# IR_detector_pcb.net
KiCad netlist of a schematic drawn in EAGLE
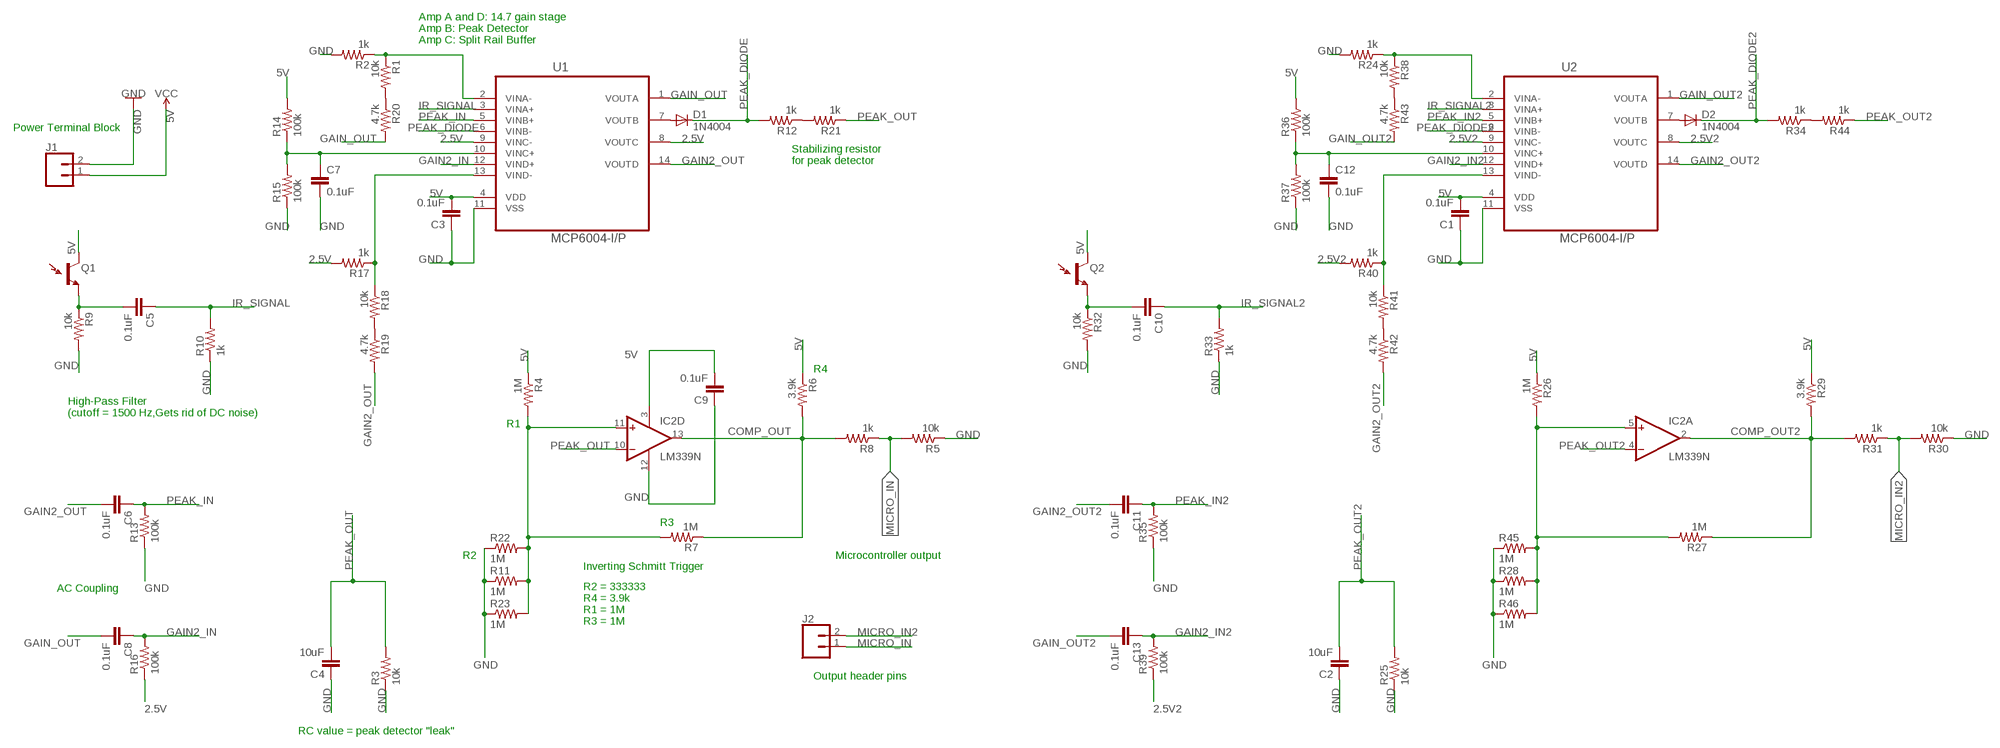
[diagram p0: schematic, sheet 1]

(export (version "E")
  (design (tool "Eeschema 10.0.6"))
  (components
    (comp (ref "C1")
      (value "0.1uF")
      (footprint "eagle-import:C025-024X044")
      (libsource (lib "eagle-import") (part "C-EU025-024X044"))
    )
    (comp (ref "C2")
      (value "10uF")
      (footprint "eagle-import:C025-024X044")
      (libsource (lib "eagle-import") (part "C-EU025-024X044"))
    )
    (comp (ref "C3")
      (value "0.1uF")
      (footprint "eagle-import:C025-024X044")
      (libsource (lib "eagle-import") (part "C-EU025-024X044"))
    )
    (comp (ref "C4")
      (value "10uF")
      (footprint "eagle-import:C025-024X044")
      (libsource (lib "eagle-import") (part "C-EU025-024X044"))
    )
    (comp (ref "C5")
      (value "0.1uF")
      (footprint "eagle-import:C025-024X044")
      (libsource (lib "eagle-import") (part "C-EU025-024X044"))
    )
    (comp (ref "C6")
      (value "0.1uF")
      (footprint "eagle-import:C025-024X044")
      (libsource (lib "eagle-import") (part "C-EU025-024X044"))
    )
    (comp (ref "C7")
      (value "0.1uF")
      (footprint "eagle-import:C025-024X044")
      (libsource (lib "eagle-import") (part "C-EU025-024X044"))
    )
    (comp (ref "C8")
      (value "0.1uF")
      (footprint "eagle-import:C025-024X044")
      (libsource (lib "eagle-import") (part "C-EU025-024X044"))
    )
    (comp (ref "C9")
      (value "0.1uF")
      (footprint "eagle-import:C025-024X044")
      (libsource (lib "eagle-import") (part "C-EU025-024X044"))
    )
    (comp (ref "C10")
      (value "0.1uF")
      (footprint "eagle-import:C025-024X044")
      (libsource (lib "eagle-import") (part "C-EU025-024X044"))
    )
    (comp (ref "C11")
      (value "0.1uF")
      (footprint "eagle-import:C025-024X044")
      (libsource (lib "eagle-import") (part "C-EU025-024X044"))
    )
    (comp (ref "C12")
      (value "0.1uF")
      (footprint "eagle-import:C025-024X044")
      (libsource (lib "eagle-import") (part "C-EU025-024X044"))
    )
    (comp (ref "C13")
      (value "0.1uF")
      (footprint "eagle-import:C025-024X044")
      (libsource (lib "eagle-import") (part "C-EU025-024X044"))
    )
    (comp (ref "D1")
      (value "1N4004")
      (footprint "eagle-import:DO41-10")
      (libsource (lib "eagle-import") (part "1N4004"))
    )
    (comp (ref "D2")
      (value "1N4004")
      (footprint "eagle-import:DO41-10")
      (libsource (lib "eagle-import") (part "1N4004"))
    )
    (comp (ref "IC2")
      (value "LM339N")
      (footprint "eagle-import:DIL14")
      (libsource (lib "eagle-import") (part "LM339N"))
    )
    (comp (ref "J1")
      (value "CONN_025MM")
      (footprint "eagle-import:SCREWTERMINAL-5MM-2")
      (libsource (lib "eagle-import") (part "CONN_025MM"))
    )
    (comp (ref "J2")
      (value "CONN_02")
      (footprint "eagle-import:1X02")
      (libsource (lib "eagle-import") (part "CONN_02"))
    )
    (comp (ref "Q1")
      (value "LTR-301")
      (footprint "eagle-import:LTR-301")
      (libsource (lib "eagle-import") (part "LTR-301"))
    )
    (comp (ref "Q2")
      (value "LTR-301")
      (footprint "eagle-import:LTR-301")
      (libsource (lib "eagle-import") (part "LTR-301"))
    )
    (comp (ref "R1")
      (value "10k")
      (footprint "eagle-import:0204V")
      (libsource (lib "eagle-import") (part "R-US_0204/2V"))
    )
    (comp (ref "R2")
      (value "1k")
      (footprint "eagle-import:0204V")
      (libsource (lib "eagle-import") (part "R-US_0204/2V"))
    )
    (comp (ref "R3")
      (value "10k")
      (footprint "eagle-import:0204V")
      (libsource (lib "eagle-import") (part "R-US_0204/2V"))
    )
    (comp (ref "R4")
      (value "1M")
      (footprint "eagle-import:0204V")
      (libsource (lib "eagle-import") (part "R-US_0204/2V"))
    )
    (comp (ref "R5")
      (value "10k")
      (footprint "eagle-import:0204V")
      (libsource (lib "eagle-import") (part "R-US_0204/2V"))
    )
    (comp (ref "R6")
      (value "3.9k")
      (footprint "eagle-import:0204V")
      (libsource (lib "eagle-import") (part "R-US_0204/2V"))
    )
    (comp (ref "R7")
      (value "1M")
      (footprint "eagle-import:0204V")
      (libsource (lib "eagle-import") (part "R-US_0204/2V"))
    )
    (comp (ref "R8")
      (value "1k")
      (footprint "eagle-import:0204V")
      (libsource (lib "eagle-import") (part "R-US_0204/2V"))
    )
    (comp (ref "R9")
      (value "10k")
      (footprint "eagle-import:0204V")
      (libsource (lib "eagle-import") (part "R-US_0204/2V"))
    )
    (comp (ref "R10")
      (value "1k")
      (footprint "eagle-import:0204V")
      (libsource (lib "eagle-import") (part "R-US_0204/2V"))
    )
    (comp (ref "R11")
      (value "1M")
      (footprint "eagle-import:0204V")
      (libsource (lib "eagle-import") (part "R-US_0204/2V"))
    )
    (comp (ref "R12")
      (value "1k")
      (footprint "eagle-import:0204V")
      (libsource (lib "eagle-import") (part "R-US_0204/2V"))
    )
    (comp (ref "R13")
      (value "100k")
      (footprint "eagle-import:0204V")
      (libsource (lib "eagle-import") (part "R-US_0204/2V"))
    )
    (comp (ref "R14")
      (value "100k")
      (footprint "eagle-import:0204V")
      (libsource (lib "eagle-import") (part "R-US_0204/2V"))
    )
    (comp (ref "R15")
      (value "100k")
      (footprint "eagle-import:0204V")
      (libsource (lib "eagle-import") (part "R-US_0204/2V"))
    )
    (comp (ref "R16")
      (value "100k")
      (footprint "eagle-import:0204V")
      (libsource (lib "eagle-import") (part "R-US_0204/2V"))
    )
    (comp (ref "R17")
      (value "1k")
      (footprint "eagle-import:0204V")
      (libsource (lib "eagle-import") (part "R-US_0204/2V"))
    )
    (comp (ref "R18")
      (value "10k")
      (footprint "eagle-import:0204V")
      (libsource (lib "eagle-import") (part "R-US_0204/2V"))
    )
    (comp (ref "R19")
      (value "4.7k")
      (footprint "eagle-import:0204V")
      (libsource (lib "eagle-import") (part "R-US_0204/2V"))
    )
    (comp (ref "R20")
      (value "4.7k")
      (footprint "eagle-import:0204V")
      (libsource (lib "eagle-import") (part "R-US_0204/2V"))
    )
    (comp (ref "R21")
      (value "1k")
      (footprint "eagle-import:0204V")
      (libsource (lib "eagle-import") (part "R-US_0204/2V"))
    )
    (comp (ref "R22")
      (value "1M")
      (footprint "eagle-import:0204V")
      (libsource (lib "eagle-import") (part "R-US_0204/2V"))
    )
    (comp (ref "R23")
      (value "1M")
      (footprint "eagle-import:0204V")
      (libsource (lib "eagle-import") (part "R-US_0204/2V"))
    )
    (comp (ref "R24")
      (value "1k")
      (footprint "eagle-import:0204V")
      (libsource (lib "eagle-import") (part "R-US_0204/2V"))
    )
    (comp (ref "R25")
      (value "10k")
      (footprint "eagle-import:0204V")
      (libsource (lib "eagle-import") (part "R-US_0204/2V"))
    )
    (comp (ref "R26")
      (value "1M")
      (footprint "eagle-import:0204V")
      (libsource (lib "eagle-import") (part "R-US_0204/2V"))
    )
    (comp (ref "R27")
      (value "1M")
      (footprint "eagle-import:0204V")
      (libsource (lib "eagle-import") (part "R-US_0204/2V"))
    )
    (comp (ref "R28")
      (value "1M")
      (footprint "eagle-import:0204V")
      (libsource (lib "eagle-import") (part "R-US_0204/2V"))
    )
    (comp (ref "R29")
      (value "3.9k")
      (footprint "eagle-import:0204V")
      (libsource (lib "eagle-import") (part "R-US_0204/2V"))
    )
    (comp (ref "R30")
      (value "10k")
      (footprint "eagle-import:0204V")
      (libsource (lib "eagle-import") (part "R-US_0204/2V"))
    )
    (comp (ref "R31")
      (value "1k")
      (footprint "eagle-import:0204V")
      (libsource (lib "eagle-import") (part "R-US_0204/2V"))
    )
    (comp (ref "R32")
      (value "10k")
      (footprint "eagle-import:0204V")
      (libsource (lib "eagle-import") (part "R-US_0204/2V"))
    )
    (comp (ref "R33")
      (value "1k")
      (footprint "eagle-import:0204V")
      (libsource (lib "eagle-import") (part "R-US_0204/2V"))
    )
    (comp (ref "R34")
      (value "1k")
      (footprint "eagle-import:0204V")
      (libsource (lib "eagle-import") (part "R-US_0204/2V"))
    )
    (comp (ref "R35")
      (value "100k")
      (footprint "eagle-import:0204V")
      (libsource (lib "eagle-import") (part "R-US_0204/2V"))
    )
    (comp (ref "R36")
      (value "100k")
      (footprint "eagle-import:0204V")
      (libsource (lib "eagle-import") (part "R-US_0204/2V"))
    )
    (comp (ref "R37")
      (value "100k")
      (footprint "eagle-import:0204V")
      (libsource (lib "eagle-import") (part "R-US_0204/2V"))
    )
    (comp (ref "R38")
      (value "10k")
      (footprint "eagle-import:0204V")
      (libsource (lib "eagle-import") (part "R-US_0204/2V"))
    )
    (comp (ref "R39")
      (value "100k")
      (footprint "eagle-import:0204V")
      (libsource (lib "eagle-import") (part "R-US_0204/2V"))
    )
    (comp (ref "R40")
      (value "1k")
      (footprint "eagle-import:0204V")
      (libsource (lib "eagle-import") (part "R-US_0204/2V"))
    )
    (comp (ref "R41")
      (value "10k")
      (footprint "eagle-import:0204V")
      (libsource (lib "eagle-import") (part "R-US_0204/2V"))
    )
    (comp (ref "R42")
      (value "4.7k")
      (footprint "eagle-import:0204V")
      (libsource (lib "eagle-import") (part "R-US_0204/2V"))
    )
    (comp (ref "R43")
      (value "4.7k")
      (footprint "eagle-import:0204V")
      (libsource (lib "eagle-import") (part "R-US_0204/2V"))
    )
    (comp (ref "R44")
      (value "1k")
      (footprint "eagle-import:0204V")
      (libsource (lib "eagle-import") (part "R-US_0204/2V"))
    )
    (comp (ref "R45")
      (value "1M")
      (footprint "eagle-import:0204V")
      (libsource (lib "eagle-import") (part "R-US_0204/2V"))
    )
    (comp (ref "R46")
      (value "1M")
      (footprint "eagle-import:0204V")
      (libsource (lib "eagle-import") (part "R-US_0204/2V"))
    )
    (comp (ref "U1")
      (value "MCP6004-I/P")
      (footprint "eagle-import:DIP254P762X533-14")
      (libsource (lib "eagle-import") (part "MCP6004-I/P"))
    )
    (comp (ref "U2")
      (value "MCP6004-I/P")
      (footprint "eagle-import:DIP254P762X533-14")
      (libsource (lib "eagle-import") (part "MCP6004-I/P"))
    )
  )
  (nets
    (net (code "1") (name "/2.5V") (class "Default")
      (node (ref "R16") (pin "1") (pinfunction "1_1") (pintype "passive"))
      (node (ref "R17") (pin "2") (pinfunction "2_2") (pintype "passive"))
      (node (ref "U1") (pin "8") (pinfunction "VOUTC_8") (pintype "output"))
      (node (ref "U1") (pin "9") (pinfunction "VINC-_9") (pintype "input"))
    )
    (net (code "2") (name "/2.5V2") (class "Default")
      (node (ref "R39") (pin "1") (pinfunction "1_1") (pintype "passive"))
      (node (ref "R40") (pin "2") (pinfunction "2_2") (pintype "passive"))
      (node (ref "U2") (pin "8") (pinfunction "VOUTC_8") (pintype "output"))
      (node (ref "U2") (pin "9") (pinfunction "VINC-_9") (pintype "input"))
    )
    (net (code "3") (name "/COMP_OUT") (class "Default")
      (node (ref "IC2") (pin "13") (pinfunction "OUT_13") (pintype "open_collector"))
      (node (ref "R6") (pin "2") (pinfunction "2_2") (pintype "passive"))
      (node (ref "R7") (pin "1") (pinfunction "1_1") (pintype "passive"))
      (node (ref "R8") (pin "2") (pinfunction "2_2") (pintype "passive"))
    )
    (net (code "4") (name "/COMP_OUT2") (class "Default")
      (node (ref "IC2") (pin "2") (pinfunction "OUT_2") (pintype "open_collector"))
      (node (ref "R27") (pin "1") (pinfunction "1_1") (pintype "passive"))
      (node (ref "R29") (pin "2") (pinfunction "2_2") (pintype "passive"))
      (node (ref "R31") (pin "2") (pinfunction "2_2") (pintype "passive"))
    )
    (net (code "5") (name "/GAIN2_IN") (class "Default")
      (node (ref "C8") (pin "1") (pinfunction "1_1") (pintype "passive"))
      (node (ref "R16") (pin "2") (pinfunction "2_2") (pintype "passive"))
      (node (ref "U1") (pin "12") (pinfunction "VIND+_12") (pintype "input"))
    )
    (net (code "6") (name "/GAIN2_IN2") (class "Default")
      (node (ref "C13") (pin "1") (pinfunction "1_1") (pintype "passive"))
      (node (ref "R39") (pin "2") (pinfunction "2_2") (pintype "passive"))
      (node (ref "U2") (pin "12") (pinfunction "VIND+_12") (pintype "input"))
    )
    (net (code "7") (name "/GAIN2_OUT") (class "Default")
      (node (ref "C6") (pin "2") (pinfunction "2_2") (pintype "passive"))
      (node (ref "R19") (pin "2") (pinfunction "2_2") (pintype "passive"))
      (node (ref "U1") (pin "14") (pinfunction "VOUTD_14") (pintype "output"))
    )
    (net (code "8") (name "/GAIN2_OUT2") (class "Default")
      (node (ref "C11") (pin "2") (pinfunction "2_2") (pintype "passive"))
      (node (ref "R42") (pin "2") (pinfunction "2_2") (pintype "passive"))
      (node (ref "U2") (pin "14") (pinfunction "VOUTD_14") (pintype "output"))
    )
    (net (code "9") (name "/GAIN_OUT") (class "Default")
      (node (ref "C8") (pin "2") (pinfunction "2_2") (pintype "passive"))
      (node (ref "R20") (pin "2") (pinfunction "2_2") (pintype "passive"))
      (node (ref "U1") (pin "1") (pinfunction "VOUTA_1") (pintype "output"))
    )
    (net (code "10") (name "/GAIN_OUT2") (class "Default")
      (node (ref "C13") (pin "2") (pinfunction "2_2") (pintype "passive"))
      (node (ref "R43") (pin "2") (pinfunction "2_2") (pintype "passive"))
      (node (ref "U2") (pin "1") (pinfunction "VOUTA_1") (pintype "output"))
    )
    (net (code "11") (name "/IR_SIGNAL") (class "Default")
      (node (ref "C5") (pin "1") (pinfunction "1_1") (pintype "passive"))
      (node (ref "R10") (pin "2") (pinfunction "2_2") (pintype "passive"))
      (node (ref "U1") (pin "3") (pinfunction "VINA+_3") (pintype "input"))
    )
    (net (code "12") (name "/IR_SIGNAL2") (class "Default")
      (node (ref "C10") (pin "1") (pinfunction "1_1") (pintype "passive"))
      (node (ref "R33") (pin "2") (pinfunction "2_2") (pintype "passive"))
      (node (ref "U2") (pin "3") (pinfunction "VINA+_3") (pintype "input"))
    )
    (net (code "13") (name "/PEAK_DIODE") (class "Default")
      (node (ref "D1") (pin "C") (pinfunction "C_C") (pintype "passive"))
      (node (ref "R12") (pin "2") (pinfunction "2_2") (pintype "passive"))
      (node (ref "U1") (pin "6") (pinfunction "VINB-_6") (pintype "input"))
    )
    (net (code "14") (name "/PEAK_DIODE2") (class "Default")
      (node (ref "D2") (pin "C") (pinfunction "C_C") (pintype "passive"))
      (node (ref "R34") (pin "2") (pinfunction "2_2") (pintype "passive"))
      (node (ref "U2") (pin "6") (pinfunction "VINB-_6") (pintype "input"))
    )
    (net (code "15") (name "/PEAK_IN") (class "Default")
      (node (ref "C6") (pin "1") (pinfunction "1_1") (pintype "passive"))
      (node (ref "R13") (pin "2") (pinfunction "2_2") (pintype "passive"))
      (node (ref "U1") (pin "5") (pinfunction "VINB+_5") (pintype "input"))
    )
    (net (code "16") (name "/PEAK_IN2") (class "Default")
      (node (ref "C11") (pin "1") (pinfunction "1_1") (pintype "passive"))
      (node (ref "R35") (pin "2") (pinfunction "2_2") (pintype "passive"))
      (node (ref "U2") (pin "5") (pinfunction "VINB+_5") (pintype "input"))
    )
    (net (code "17") (name "/PEAK_OUT") (class "Default")
      (node (ref "C4") (pin "2") (pinfunction "2_2") (pintype "passive"))
      (node (ref "IC2") (pin "10") (pinfunction "-IN_10") (pintype "input"))
      (node (ref "R21") (pin "1") (pinfunction "1_1") (pintype "passive"))
      (node (ref "R3") (pin "2") (pinfunction "2_2") (pintype "passive"))
    )
    (net (code "18") (name "/PEAK_OUT2") (class "Default")
      (node (ref "C2") (pin "2") (pinfunction "2_2") (pintype "passive"))
      (node (ref "IC2") (pin "4") (pinfunction "-IN_4") (pintype "input"))
      (node (ref "R25") (pin "2") (pinfunction "2_2") (pintype "passive"))
      (node (ref "R44") (pin "1") (pinfunction "1_1") (pintype "passive"))
    )
    (net (code "19") (name "GND") (class "Default")
      (node (ref "C1") (pin "1") (pinfunction "1_1") (pintype "passive"))
      (node (ref "C12") (pin "2") (pinfunction "2_2") (pintype "passive"))
      (node (ref "C2") (pin "1") (pinfunction "1_1") (pintype "passive"))
      (node (ref "C3") (pin "1") (pinfunction "1_1") (pintype "passive"))
      (node (ref "C4") (pin "1") (pinfunction "1_1") (pintype "passive"))
      (node (ref "C7") (pin "2") (pinfunction "2_2") (pintype "passive"))
      (node (ref "C9") (pin "1") (pinfunction "1_1") (pintype "passive"))
      (node (ref "IC2") (pin "12") (pinfunction "GND_12") (pintype "power_in"))
      (node (ref "J1") (pin "2") (pinfunction "2_2") (pintype "passive"))
      (node (ref "R10") (pin "1") (pinfunction "1_1") (pintype "passive"))
      (node (ref "R11") (pin "1") (pinfunction "1_1") (pintype "passive"))
      (node (ref "R13") (pin "1") (pinfunction "1_1") (pintype "passive"))
      (node (ref "R15") (pin "1") (pinfunction "1_1") (pintype "passive"))
      (node (ref "R2") (pin "2") (pinfunction "2_2") (pintype "passive"))
      (node (ref "R22") (pin "1") (pinfunction "1_1") (pintype "passive"))
      (node (ref "R23") (pin "1") (pinfunction "1_1") (pintype "passive"))
      (node (ref "R24") (pin "2") (pinfunction "2_2") (pintype "passive"))
      (node (ref "R25") (pin "1") (pinfunction "1_1") (pintype "passive"))
      (node (ref "R28") (pin "1") (pinfunction "1_1") (pintype "passive"))
      (node (ref "R3") (pin "1") (pinfunction "1_1") (pintype "passive"))
      (node (ref "R30") (pin "1") (pinfunction "1_1") (pintype "passive"))
      (node (ref "R32") (pin "2") (pinfunction "2_2") (pintype "passive"))
      (node (ref "R33") (pin "1") (pinfunction "1_1") (pintype "passive"))
      (node (ref "R35") (pin "1") (pinfunction "1_1") (pintype "passive"))
      (node (ref "R37") (pin "1") (pinfunction "1_1") (pintype "passive"))
      (node (ref "R45") (pin "1") (pinfunction "1_1") (pintype "passive"))
      (node (ref "R46") (pin "1") (pinfunction "1_1") (pintype "passive"))
      (node (ref "R5") (pin "1") (pinfunction "1_1") (pintype "passive"))
      (node (ref "R9") (pin "2") (pinfunction "2_2") (pintype "passive"))
      (node (ref "U1") (pin "11") (pinfunction "VSS_11") (pintype "passive"))
      (node (ref "U2") (pin "11") (pinfunction "VSS_11") (pintype "passive"))
    )
    (net (code "20") (name "MICRO_IN") (class "Default")
      (node (ref "J2") (pin "1") (pinfunction "1_1") (pintype "passive"))
      (node (ref "R5") (pin "2") (pinfunction "2_2") (pintype "passive"))
      (node (ref "R8") (pin "1") (pinfunction "1_1") (pintype "passive"))
    )
    (net (code "21") (name "MICRO_IN2") (class "Default")
      (node (ref "J2") (pin "2") (pinfunction "2_2") (pintype "passive"))
      (node (ref "R30") (pin "2") (pinfunction "2_2") (pintype "passive"))
      (node (ref "R31") (pin "1") (pinfunction "1_1") (pintype "passive"))
    )
    (net (code "22") (name "Net-(IC2A-+IN)") (class "Default")
      (node (ref "IC2") (pin "5") (pinfunction "+IN_5") (pintype "input"))
      (node (ref "R26") (pin "2") (pinfunction "2_2") (pintype "passive"))
      (node (ref "R27") (pin "2") (pinfunction "2_2") (pintype "passive"))
      (node (ref "R28") (pin "2") (pinfunction "2_2") (pintype "passive"))
      (node (ref "R45") (pin "2") (pinfunction "2_2") (pintype "passive"))
      (node (ref "R46") (pin "2") (pinfunction "2_2") (pintype "passive"))
    )
    (net (code "23") (name "Net-(IC2D-+IN)") (class "Default")
      (node (ref "IC2") (pin "11") (pinfunction "+IN_11") (pintype "input"))
      (node (ref "R11") (pin "2") (pinfunction "2_2") (pintype "passive"))
      (node (ref "R22") (pin "2") (pinfunction "2_2") (pintype "passive"))
      (node (ref "R23") (pin "2") (pinfunction "2_2") (pintype "passive"))
      (node (ref "R4") (pin "2") (pinfunction "2_2") (pintype "passive"))
      (node (ref "R7") (pin "2") (pinfunction "2_2") (pintype "passive"))
    )
    (net (code "24") (name "Net-(Q1-E1)") (class "Default")
      (node (ref "C5") (pin "2") (pinfunction "2_2") (pintype "passive"))
      (node (ref "Q1") (pin "E") (pinfunction "E1_E") (pintype "passive"))
      (node (ref "R9") (pin "1") (pinfunction "1_1") (pintype "passive"))
    )
    (net (code "25") (name "Net-(Q2-E1)") (class "Default")
      (node (ref "C10") (pin "2") (pinfunction "2_2") (pintype "passive"))
      (node (ref "Q2") (pin "E") (pinfunction "E1_E") (pintype "passive"))
      (node (ref "R32") (pin "1") (pinfunction "1_1") (pintype "passive"))
    )
    (net (code "26") (name "Net-(R1-Pad2)") (class "Default")
      (node (ref "R1") (pin "2") (pinfunction "2_2") (pintype "passive"))
      (node (ref "R20") (pin "1") (pinfunction "1_1") (pintype "passive"))
    )
    (net (code "27") (name "Net-(R12-Pad1)") (class "Default")
      (node (ref "R12") (pin "1") (pinfunction "1_1") (pintype "passive"))
      (node (ref "R21") (pin "2") (pinfunction "2_2") (pintype "passive"))
    )
    (net (code "28") (name "Net-(R18-Pad2)") (class "Default")
      (node (ref "R18") (pin "2") (pinfunction "2_2") (pintype "passive"))
      (node (ref "R19") (pin "1") (pinfunction "1_1") (pintype "passive"))
    )
    (net (code "29") (name "Net-(R34-Pad1)") (class "Default")
      (node (ref "R34") (pin "1") (pinfunction "1_1") (pintype "passive"))
      (node (ref "R44") (pin "2") (pinfunction "2_2") (pintype "passive"))
    )
    (net (code "30") (name "Net-(R38-Pad2)") (class "Default")
      (node (ref "R38") (pin "2") (pinfunction "2_2") (pintype "passive"))
      (node (ref "R43") (pin "1") (pinfunction "1_1") (pintype "passive"))
    )
    (net (code "31") (name "Net-(R41-Pad2)") (class "Default")
      (node (ref "R41") (pin "2") (pinfunction "2_2") (pintype "passive"))
      (node (ref "R42") (pin "1") (pinfunction "1_1") (pintype "passive"))
    )
    (net (code "32") (name "Net-(U1-VINA-)") (class "Default")
      (node (ref "R1") (pin "1") (pinfunction "1_1") (pintype "passive"))
      (node (ref "R2") (pin "1") (pinfunction "1_1") (pintype "passive"))
      (node (ref "U1") (pin "2") (pinfunction "VINA-_2") (pintype "input"))
    )
    (net (code "33") (name "Net-(U1-VINC+)") (class "Default")
      (node (ref "C7") (pin "1") (pinfunction "1_1") (pintype "passive"))
      (node (ref "R14") (pin "1") (pinfunction "1_1") (pintype "passive"))
      (node (ref "R15") (pin "2") (pinfunction "2_2") (pintype "passive"))
      (node (ref "U1") (pin "10") (pinfunction "VINC+_10") (pintype "input"))
    )
    (net (code "34") (name "Net-(U1-VIND-)") (class "Default")
      (node (ref "R17") (pin "1") (pinfunction "1_1") (pintype "passive"))
      (node (ref "R18") (pin "1") (pinfunction "1_1") (pintype "passive"))
      (node (ref "U1") (pin "13") (pinfunction "VIND-_13") (pintype "input"))
    )
    (net (code "35") (name "Net-(U1-VOUTB)") (class "Default")
      (node (ref "D1") (pin "A") (pinfunction "A_A") (pintype "passive"))
      (node (ref "U1") (pin "7") (pinfunction "VOUTB_7") (pintype "output"))
    )
    (net (code "36") (name "Net-(U2-VINA-)") (class "Default")
      (node (ref "R24") (pin "1") (pinfunction "1_1") (pintype "passive"))
      (node (ref "R38") (pin "1") (pinfunction "1_1") (pintype "passive"))
      (node (ref "U2") (pin "2") (pinfunction "VINA-_2") (pintype "input"))
    )
    (net (code "37") (name "Net-(U2-VINC+)") (class "Default")
      (node (ref "C12") (pin "1") (pinfunction "1_1") (pintype "passive"))
      (node (ref "R36") (pin "1") (pinfunction "1_1") (pintype "passive"))
      (node (ref "R37") (pin "2") (pinfunction "2_2") (pintype "passive"))
      (node (ref "U2") (pin "10") (pinfunction "VINC+_10") (pintype "input"))
    )
    (net (code "38") (name "Net-(U2-VIND-)") (class "Default")
      (node (ref "R40") (pin "1") (pinfunction "1_1") (pintype "passive"))
      (node (ref "R41") (pin "1") (pinfunction "1_1") (pintype "passive"))
      (node (ref "U2") (pin "13") (pinfunction "VIND-_13") (pintype "input"))
    )
    (net (code "39") (name "Net-(U2-VOUTB)") (class "Default")
      (node (ref "D2") (pin "A") (pinfunction "A_A") (pintype "passive"))
      (node (ref "U2") (pin "7") (pinfunction "VOUTB_7") (pintype "output"))
    )
    (net (code "40") (name "VCC") (class "Default")
      (node (ref "C1") (pin "2") (pinfunction "2_2") (pintype "passive"))
      (node (ref "C3") (pin "2") (pinfunction "2_2") (pintype "passive"))
      (node (ref "C9") (pin "2") (pinfunction "2_2") (pintype "passive"))
      (node (ref "IC2") (pin "3") (pinfunction "V+_3") (pintype "power_in"))
      (node (ref "J1") (pin "1") (pinfunction "1_1") (pintype "passive"))
      (node (ref "Q1") (pin "C") (pinfunction "C1_C") (pintype "passive"))
      (node (ref "Q2") (pin "C") (pinfunction "C1_C") (pintype "passive"))
      (node (ref "R14") (pin "2") (pinfunction "2_2") (pintype "passive"))
      (node (ref "R26") (pin "1") (pinfunction "1_1") (pintype "passive"))
      (node (ref "R29") (pin "1") (pinfunction "1_1") (pintype "passive"))
      (node (ref "R36") (pin "2") (pinfunction "2_2") (pintype "passive"))
      (node (ref "R4") (pin "1") (pinfunction "1_1") (pintype "passive"))
      (node (ref "R6") (pin "1") (pinfunction "1_1") (pintype "passive"))
      (node (ref "U1") (pin "4") (pinfunction "VDD_4") (pintype "power_in"))
      (node (ref "U2") (pin "4") (pinfunction "VDD_4") (pintype "power_in"))
    )
  )
)
